# schematic.net
KiCad netlist of a schematic drawn in EAGLE
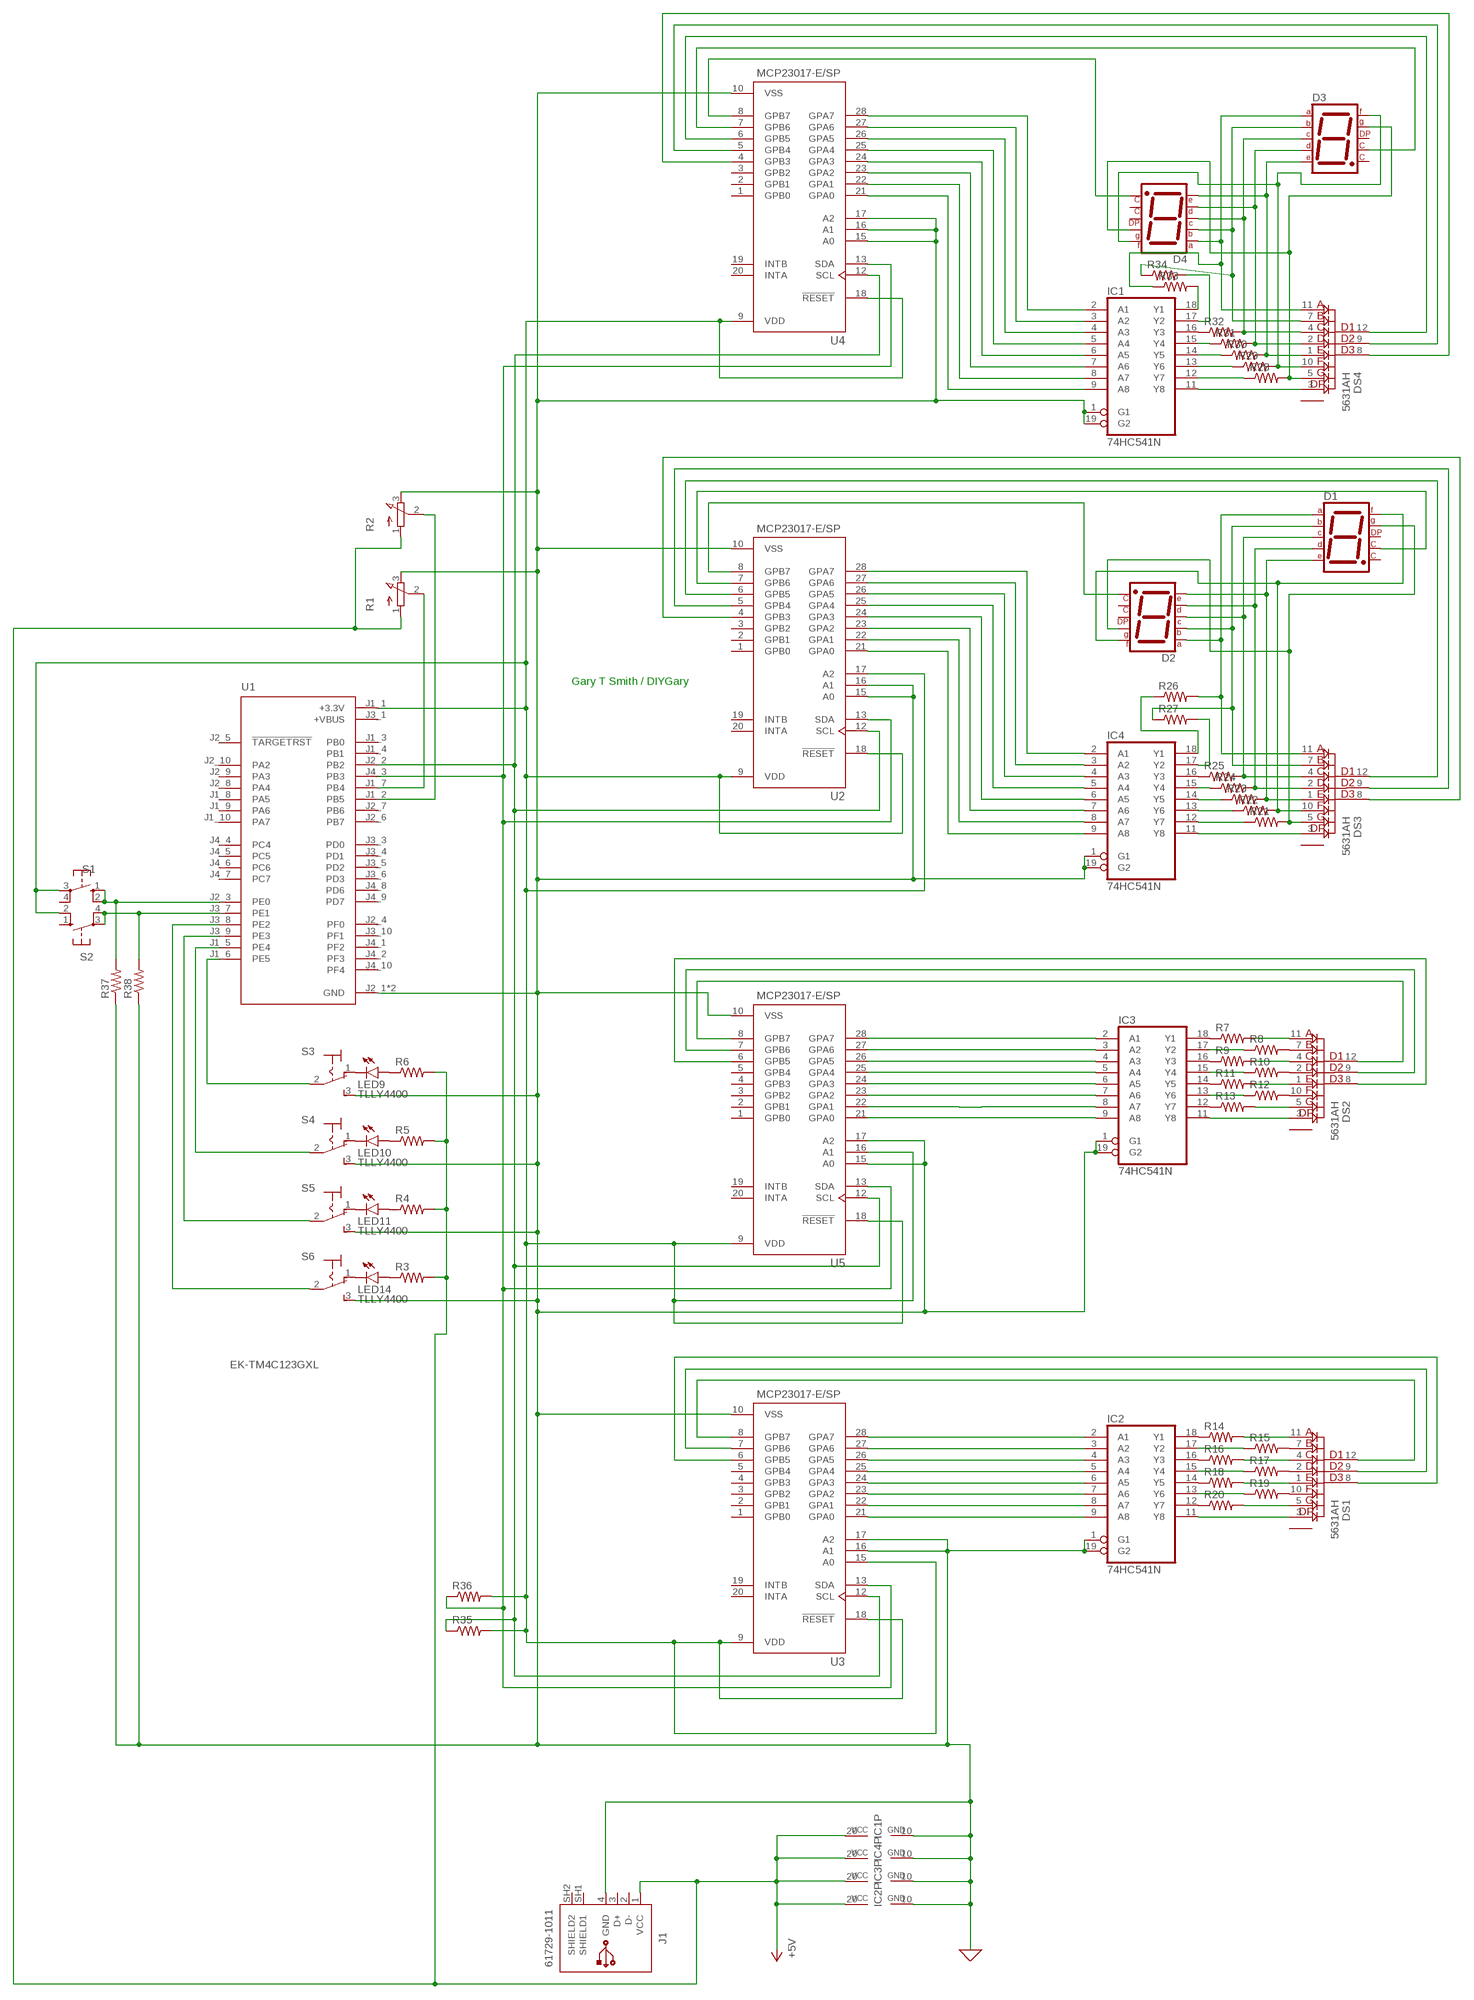
[diagram p0: schematic, sheet 1]

(export (version "E")
  (design (tool "Eeschema 10.0.6"))
  (components
    (comp (ref "D1")
      (value "5611AH")
      (footprint "eagle-import:5611AH")
      (libsource (lib "eagle-import") (part "5611AH"))
    )
    (comp (ref "D2")
      (value "5611AH")
      (footprint "eagle-import:5611AH")
      (libsource (lib "eagle-import") (part "5611AH"))
    )
    (comp (ref "D3")
      (value "5611AH")
      (footprint "eagle-import:5611AH")
      (libsource (lib "eagle-import") (part "5611AH"))
    )
    (comp (ref "D4")
      (value "5611AH")
      (footprint "eagle-import:5611AH")
      (libsource (lib "eagle-import") (part "5611AH"))
    )
    (comp (ref "DS1")
      (value "5631AH")
      (footprint "eagle-import:DIPS1524W50P254L3760H835Q12N")
      (fields
        (field (name "MANUFACTURER_PART_NUMBER") "BC56-12SRWA")
        (field (name "MOUSER_PART_NUMBER") "604-BC56-12SRWA")
      )
      (libsource (lib "eagle-import") (part "5631AH"))
    )
    (comp (ref "DS2")
      (value "5631AH")
      (footprint "eagle-import:DIPS1524W50P254L3760H835Q12N")
      (fields
        (field (name "MANUFACTURER_PART_NUMBER") "BC56-12SRWA")
        (field (name "MOUSER_PART_NUMBER") "604-BC56-12SRWA")
      )
      (libsource (lib "eagle-import") (part "5631AH"))
    )
    (comp (ref "DS3")
      (value "5631AH")
      (footprint "eagle-import:DIPS1524W50P254L3760H835Q12N")
      (fields
        (field (name "MANUFACTURER_PART_NUMBER") "BC56-12SRWA")
        (field (name "MOUSER_PART_NUMBER") "604-BC56-12SRWA")
      )
      (libsource (lib "eagle-import") (part "5631AH"))
    )
    (comp (ref "DS4")
      (value "5631AH")
      (footprint "eagle-import:DIPS1524W50P254L3760H835Q12N")
      (fields
        (field (name "MANUFACTURER_PART_NUMBER") "BC56-12SRWA")
        (field (name "MOUSER_PART_NUMBER") "604-BC56-12SRWA")
      )
      (libsource (lib "eagle-import") (part "5631AH"))
    )
    (comp (ref "IC1")
      (value "74HC541N")
      (footprint "eagle-import:DIL20")
      (libsource (lib "eagle-import") (part "74541NHC"))
    )
    (comp (ref "IC2")
      (value "74HC541N")
      (footprint "eagle-import:DIL20")
      (libsource (lib "eagle-import") (part "74541NHC"))
    )
    (comp (ref "IC3")
      (value "74HC541N")
      (footprint "eagle-import:DIL20")
      (libsource (lib "eagle-import") (part "74541NHC"))
    )
    (comp (ref "IC4")
      (value "74HC541N")
      (footprint "eagle-import:DIL20")
      (libsource (lib "eagle-import") (part "74541NHC"))
    )
    (comp (ref "J1")
      (value "61729-1011")
      (footprint "eagle-import:61729-1011BLF")
      (fields (field (name "MANUFACTURER") "Amphenol ICC (FCI)") (field (name "MPN") "61729-1011BLF"))
      (libsource (lib "eagle-import") (part "61729-1011"))
    )
    (comp (ref "LED9")
      (value "TLLY4400")
      (footprint "eagle-import:LED3MM")
      (fields (field (name "MF") "VISHAY SEMICONDUCTOR"))
      (libsource (lib "eagle-import") (part "TLLY4400"))
    )
    (comp (ref "LED10")
      (value "TLLY4400")
      (footprint "eagle-import:LED3MM")
      (fields (field (name "MF") "VISHAY SEMICONDUCTOR"))
      (libsource (lib "eagle-import") (part "TLLY4400"))
    )
    (comp (ref "LED11")
      (value "TLLY4400")
      (footprint "eagle-import:LED3MM")
      (fields (field (name "MF") "VISHAY SEMICONDUCTOR"))
      (libsource (lib "eagle-import") (part "TLLY4400"))
    )
    (comp (ref "LED14")
      (value "TLLY4400")
      (footprint "eagle-import:LED3MM")
      (fields (field (name "MF") "VISHAY SEMICONDUCTOR"))
      (libsource (lib "eagle-import") (part "TLLY4400"))
    )
    (comp (ref "R1")
      (value "3RP/1610N")
      (footprint "eagle-import:3RP_1610N")
      (libsource (lib "eagle-import") (part "3RP/1610N"))
    )
    (comp (ref "R2")
      (value "3RP/1610N")
      (footprint "eagle-import:3RP_1610N")
      (libsource (lib "eagle-import") (part "3RP/1610N"))
    )
    (comp (ref "R3")
      (value "R-US_0204/7")
      (footprint "eagle-import:0204_7")
      (libsource (lib "eagle-import") (part "R-US_0204/7"))
    )
    (comp (ref "R4")
      (value "R-US_0204/7")
      (footprint "eagle-import:0204_7")
      (libsource (lib "eagle-import") (part "R-US_0204/7"))
    )
    (comp (ref "R5")
      (value "R-US_0204/7")
      (footprint "eagle-import:0204_7")
      (libsource (lib "eagle-import") (part "R-US_0204/7"))
    )
    (comp (ref "R6")
      (value "R-US_0204/7")
      (footprint "eagle-import:0204_7")
      (libsource (lib "eagle-import") (part "R-US_0204/7"))
    )
    (comp (ref "R7")
      (value "R-US_0204/7")
      (footprint "eagle-import:0204_7")
      (libsource (lib "eagle-import") (part "R-US_0204/7"))
    )
    (comp (ref "R8")
      (value "R-US_0204/7")
      (footprint "eagle-import:0204_7")
      (libsource (lib "eagle-import") (part "R-US_0204/7"))
    )
    (comp (ref "R9")
      (value "R-US_0204/7")
      (footprint "eagle-import:0204_7")
      (libsource (lib "eagle-import") (part "R-US_0204/7"))
    )
    (comp (ref "R10")
      (value "R-US_0204/7")
      (footprint "eagle-import:0204_7")
      (libsource (lib "eagle-import") (part "R-US_0204/7"))
    )
    (comp (ref "R11")
      (value "R-US_0204/7")
      (footprint "eagle-import:0204_7")
      (libsource (lib "eagle-import") (part "R-US_0204/7"))
    )
    (comp (ref "R12")
      (value "R-US_0204/7")
      (footprint "eagle-import:0204_7")
      (libsource (lib "eagle-import") (part "R-US_0204/7"))
    )
    (comp (ref "R13")
      (value "R-US_0204/7")
      (footprint "eagle-import:0204_7")
      (libsource (lib "eagle-import") (part "R-US_0204/7"))
    )
    (comp (ref "R14")
      (value "R-US_0204/7")
      (footprint "eagle-import:0204_7")
      (libsource (lib "eagle-import") (part "R-US_0204/7"))
    )
    (comp (ref "R15")
      (value "R-US_0204/7")
      (footprint "eagle-import:0204_7")
      (libsource (lib "eagle-import") (part "R-US_0204/7"))
    )
    (comp (ref "R16")
      (value "R-US_0204/7")
      (footprint "eagle-import:0204_7")
      (libsource (lib "eagle-import") (part "R-US_0204/7"))
    )
    (comp (ref "R17")
      (value "R-US_0204/7")
      (footprint "eagle-import:0204_7")
      (libsource (lib "eagle-import") (part "R-US_0204/7"))
    )
    (comp (ref "R18")
      (value "R-US_0204/7")
      (footprint "eagle-import:0204_7")
      (libsource (lib "eagle-import") (part "R-US_0204/7"))
    )
    (comp (ref "R19")
      (value "R-US_0204/7")
      (footprint "eagle-import:0204_7")
      (libsource (lib "eagle-import") (part "R-US_0204/7"))
    )
    (comp (ref "R20")
      (value "R-US_0204/7")
      (footprint "eagle-import:0204_7")
      (libsource (lib "eagle-import") (part "R-US_0204/7"))
    )
    (comp (ref "R21")
      (value "R-US_0204/7")
      (footprint "eagle-import:0204_7")
      (libsource (lib "eagle-import") (part "R-US_0204/7"))
    )
    (comp (ref "R22")
      (value "R-US_0204/7")
      (footprint "eagle-import:0204_7")
      (libsource (lib "eagle-import") (part "R-US_0204/7"))
    )
    (comp (ref "R23")
      (value "R-US_0204/7")
      (footprint "eagle-import:0204_7")
      (libsource (lib "eagle-import") (part "R-US_0204/7"))
    )
    (comp (ref "R24")
      (value "R-US_0204/7")
      (footprint "eagle-import:0204_7")
      (libsource (lib "eagle-import") (part "R-US_0204/7"))
    )
    (comp (ref "R25")
      (value "R-US_0204/7")
      (footprint "eagle-import:0204_7")
      (libsource (lib "eagle-import") (part "R-US_0204/7"))
    )
    (comp (ref "R26")
      (value "R-US_0204/7")
      (footprint "eagle-import:0204_7")
      (libsource (lib "eagle-import") (part "R-US_0204/7"))
    )
    (comp (ref "R27")
      (value "R-US_0204/7")
      (footprint "eagle-import:0204_7")
      (libsource (lib "eagle-import") (part "R-US_0204/7"))
    )
    (comp (ref "R28")
      (value "R-US_0204/7")
      (footprint "eagle-import:0204_7")
      (libsource (lib "eagle-import") (part "R-US_0204/7"))
    )
    (comp (ref "R29")
      (value "R-US_0204/7")
      (footprint "eagle-import:0204_7")
      (libsource (lib "eagle-import") (part "R-US_0204/7"))
    )
    (comp (ref "R30")
      (value "R-US_0204/7")
      (footprint "eagle-import:0204_7")
      (libsource (lib "eagle-import") (part "R-US_0204/7"))
    )
    (comp (ref "R31")
      (value "R-US_0204/7")
      (footprint "eagle-import:0204_7")
      (libsource (lib "eagle-import") (part "R-US_0204/7"))
    )
    (comp (ref "R32")
      (value "R-US_0204/7")
      (footprint "eagle-import:0204_7")
      (libsource (lib "eagle-import") (part "R-US_0204/7"))
    )
    (comp (ref "R33")
      (value "R-US_0204/7")
      (footprint "eagle-import:0204_7")
      (libsource (lib "eagle-import") (part "R-US_0204/7"))
    )
    (comp (ref "R34")
      (value "R-US_0204/7")
      (footprint "eagle-import:0204_7")
      (libsource (lib "eagle-import") (part "R-US_0204/7"))
    )
    (comp (ref "R35")
      (value "R-US_0204/7")
      (footprint "eagle-import:0204_7")
      (libsource (lib "eagle-import") (part "R-US_0204/7"))
    )
    (comp (ref "R36")
      (value "R-US_0204/7")
      (footprint "eagle-import:0204_7")
      (libsource (lib "eagle-import") (part "R-US_0204/7"))
    )
    (comp (ref "R37")
      (value "R-US_0204/7")
      (footprint "eagle-import:0204_7")
      (libsource (lib "eagle-import") (part "R-US_0204/7"))
    )
    (comp (ref "R38")
      (value "R-US_0204/7")
      (footprint "eagle-import:0204_7")
      (libsource (lib "eagle-import") (part "R-US_0204/7"))
    )
    (comp (ref "S1")
      (value "10-XX")
      (footprint "eagle-import:B3F-10XX")
      (fields (field (name "MPN") "B3F-1000"))
      (libsource (lib "eagle-import") (part "10-XX"))
    )
    (comp (ref "S2")
      (value "10-XX")
      (footprint "eagle-import:B3F-10XX")
      (fields (field (name "MPN") "B3F-1000"))
      (libsource (lib "eagle-import") (part "10-XX"))
    )
    (comp (ref "S3")
      (value "320-916")
      (footprint "eagle-import:320-916")
      (libsource (lib "eagle-import") (part "320-916"))
    )
    (comp (ref "S4")
      (value "320-916")
      (footprint "eagle-import:320-916")
      (libsource (lib "eagle-import") (part "320-916"))
    )
    (comp (ref "S5")
      (value "320-916")
      (footprint "eagle-import:320-916")
      (libsource (lib "eagle-import") (part "320-916"))
    )
    (comp (ref "S6")
      (value "320-916")
      (footprint "eagle-import:320-916")
      (libsource (lib "eagle-import") (part "320-916"))
    )
    (comp (ref "U1")
      (value "EK-TM4C123GXL")
      (footprint "eagle-import:MODULE_EK-TM4C123GXL")
      (fields (field (name "MF") "Texas Instruments"))
      (libsource (lib "eagle-import") (part "EK-TM4C123GXL"))
    )
    (comp (ref "U2")
      (value "MCP23017-E/SP")
      (footprint "eagle-import:DIP787W45P254L3556H508Q28")
      (fields (field (name "MF") "Microchip Technology"))
      (libsource (lib "eagle-import") (part "MCP23017-E/SP"))
    )
    (comp (ref "U3")
      (value "MCP23017-E/SP")
      (footprint "eagle-import:DIP787W45P254L3556H508Q28")
      (fields (field (name "MF") "Microchip Technology"))
      (libsource (lib "eagle-import") (part "MCP23017-E/SP"))
    )
    (comp (ref "U4")
      (value "MCP23017-E/SP")
      (footprint "eagle-import:DIP787W45P254L3556H508Q28")
      (fields (field (name "MF") "Microchip Technology"))
      (libsource (lib "eagle-import") (part "MCP23017-E/SP"))
    )
    (comp (ref "U5")
      (value "MCP23017-E/SP")
      (footprint "eagle-import:DIP787W45P254L3556H508Q28")
      (fields (field (name "MF") "Microchip Technology"))
      (libsource (lib "eagle-import") (part "MCP23017-E/SP"))
    )
  )
  (nets
    (net (code "1") (name "+5V") (class "Default")
      (node (ref "IC1") (pin "20") (pinfunction "VCC_20") (pintype "power_in"))
      (node (ref "IC2") (pin "20") (pinfunction "VCC_20") (pintype "power_in"))
      (node (ref "IC3") (pin "20") (pinfunction "VCC_20") (pintype "power_in"))
      (node (ref "IC4") (pin "20") (pinfunction "VCC_20") (pintype "power_in"))
      (node (ref "J1") (pin "1") (pinfunction "VCC_1") (pintype "power_in"))
      (node (ref "R1") (pin "1") (pinfunction "A_1") (pintype "passive"))
      (node (ref "R2") (pin "1") (pinfunction "A_1") (pintype "passive"))
      (node (ref "R3") (pin "2") (pinfunction "2_2") (pintype "passive"))
      (node (ref "R4") (pin "2") (pinfunction "2_2") (pintype "passive"))
      (node (ref "R5") (pin "2") (pinfunction "2_2") (pintype "passive"))
      (node (ref "R6") (pin "2") (pinfunction "2_2") (pintype "passive"))
    )
    (net (code "2") (name "/+VBUS") (class "Default")
      (node (ref "U1") (pin "J3_1") (pinfunction "+VBUS_J3_1") (pintype "power_in"))
    )
    (net (code "3") (name "/SHIELD1") (class "Default")
      (node (ref "J1") (pin "SH1") (pinfunction "SHIELD1_SH1") (pintype "power_in"))
    )
    (net (code "4") (name "/SHIELD2") (class "Default")
      (node (ref "J1") (pin "SH2") (pinfunction "SHIELD2_SH2") (pintype "power_in"))
    )
    (net (code "5") (name "GND") (class "Default")
      (node (ref "IC1") (pin "1") (pinfunction "G1_1") (pintype "input"))
      (node (ref "IC1") (pin "10") (pinfunction "GND_10") (pintype "power_in"))
      (node (ref "IC1") (pin "19") (pinfunction "G2_19") (pintype "input"))
      (node (ref "IC2") (pin "1") (pinfunction "G1_1") (pintype "input"))
      (node (ref "IC2") (pin "10") (pinfunction "GND_10") (pintype "power_in"))
      (node (ref "IC2") (pin "19") (pinfunction "G2_19") (pintype "input"))
      (node (ref "IC3") (pin "1") (pinfunction "G1_1") (pintype "input"))
      (node (ref "IC3") (pin "10") (pinfunction "GND_10") (pintype "power_in"))
      (node (ref "IC3") (pin "19") (pinfunction "G2_19") (pintype "input"))
      (node (ref "IC4") (pin "1") (pinfunction "G1_1") (pintype "input"))
      (node (ref "IC4") (pin "10") (pinfunction "GND_10") (pintype "power_in"))
      (node (ref "IC4") (pin "19") (pinfunction "G2_19") (pintype "input"))
      (node (ref "J1") (pin "4") (pinfunction "GND_4") (pintype "power_in"))
      (node (ref "R1") (pin "3") (pinfunction "E_3") (pintype "passive"))
      (node (ref "R2") (pin "3") (pinfunction "E_3") (pintype "passive"))
      (node (ref "R37") (pin "1") (pinfunction "1_1") (pintype "passive"))
      (node (ref "R38") (pin "1") (pinfunction "1_1") (pintype "passive"))
      (node (ref "S3") (pin "3") (pinfunction "S_3") (pintype "passive"))
      (node (ref "S4") (pin "3") (pinfunction "S_3") (pintype "passive"))
      (node (ref "S5") (pin "3") (pinfunction "S_3") (pintype "passive"))
      (node (ref "S6") (pin "3") (pinfunction "S_3") (pintype "passive"))
      (node (ref "U1") (pin "J2_1") (pinfunction "GND_J2_1") (pintype "power_in"))
      (node (ref "U1") (pin "J3_2") (pinfunction "GND_J3_2") (pintype "power_in"))
      (node (ref "U2") (pin "10") (pinfunction "VSS_10") (pintype "power_in"))
      (node (ref "U2") (pin "15") (pinfunction "A0_15") (pintype "input"))
      (node (ref "U2") (pin "16") (pinfunction "A1_16") (pintype "input"))
      (node (ref "U3") (pin "10") (pinfunction "VSS_10") (pintype "power_in"))
      (node (ref "U3") (pin "16") (pinfunction "A1_16") (pintype "input"))
      (node (ref "U3") (pin "17") (pinfunction "A2_17") (pintype "input"))
      (node (ref "U4") (pin "10") (pinfunction "VSS_10") (pintype "power_in"))
      (node (ref "U4") (pin "15") (pinfunction "A0_15") (pintype "input"))
      (node (ref "U4") (pin "16") (pinfunction "A1_16") (pintype "input"))
      (node (ref "U4") (pin "17") (pinfunction "A2_17") (pintype "input"))
      (node (ref "U5") (pin "10") (pinfunction "VSS_10") (pintype "power_in"))
      (node (ref "U5") (pin "15") (pinfunction "A0_15") (pintype "input"))
      (node (ref "U5") (pin "17") (pinfunction "A2_17") (pintype "input"))
    )
    (net (code "6") (name "Net-(D1-A)") (class "Default")
      (node (ref "D1") (pin "7") (pinfunction "A_7") (pintype "passive"))
      (node (ref "D2") (pin "7") (pinfunction "A_7") (pintype "passive"))
      (node (ref "DS3") (pin "11") (pinfunction "A_A_11") (pintype "bidirectional"))
      (node (ref "R26") (pin "2") (pinfunction "2_2") (pintype "passive"))
    )
    (net (code "7") (name "Net-(D1-B)") (class "Default")
      (node (ref "D1") (pin "6") (pinfunction "B_6") (pintype "passive"))
      (node (ref "D2") (pin "6") (pinfunction "B_6") (pintype "passive"))
      (node (ref "DS3") (pin "7") (pinfunction "A_B_7") (pintype "bidirectional"))
      (node (ref "R27") (pin "1") (pinfunction "1_1") (pintype "passive"))
    )
    (net (code "8") (name "Net-(D1-C)") (class "Default")
      (node (ref "D1") (pin "4") (pinfunction "C_4") (pintype "passive"))
      (node (ref "D2") (pin "4") (pinfunction "C_4") (pintype "passive"))
      (node (ref "DS3") (pin "4") (pinfunction "A_C_4") (pintype "bidirectional"))
      (node (ref "R25") (pin "2") (pinfunction "2_2") (pintype "passive"))
    )
    (net (code "9") (name "Net-(D1-CK1)") (class "Default")
      (node (ref "D1") (pin "3") (pinfunction "CK1_3") (pintype "passive"))
      (node (ref "U2") (pin "7") (pinfunction "GPB6_7") (pintype "bidirectional"))
    )
    (net (code "10") (name "Net-(D1-D)") (class "Default")
      (node (ref "D1") (pin "2") (pinfunction "D_2") (pintype "passive"))
      (node (ref "D2") (pin "2") (pinfunction "D_2") (pintype "passive"))
      (node (ref "DS3") (pin "2") (pinfunction "A_D_2") (pintype "bidirectional"))
      (node (ref "R24") (pin "2") (pinfunction "2_2") (pintype "passive"))
    )
    (net (code "11") (name "Net-(D1-E)") (class "Default")
      (node (ref "D1") (pin "1") (pinfunction "E_1") (pintype "passive"))
      (node (ref "D2") (pin "1") (pinfunction "E_1") (pintype "passive"))
      (node (ref "DS3") (pin "1") (pinfunction "A_E_1") (pintype "bidirectional"))
      (node (ref "R23") (pin "2") (pinfunction "2_2") (pintype "passive"))
    )
    (net (code "12") (name "Net-(D1-F)") (class "Default")
      (node (ref "D1") (pin "9") (pinfunction "F_9") (pintype "passive"))
      (node (ref "D2") (pin "9") (pinfunction "F_9") (pintype "passive"))
      (node (ref "DS3") (pin "10") (pinfunction "A_F_10") (pintype "bidirectional"))
      (node (ref "R22") (pin "2") (pinfunction "2_2") (pintype "passive"))
    )
    (net (code "13") (name "Net-(D1-G)") (class "Default")
      (node (ref "D1") (pin "10") (pinfunction "G_10") (pintype "passive"))
      (node (ref "D2") (pin "10") (pinfunction "G_10") (pintype "passive"))
      (node (ref "DS3") (pin "5") (pinfunction "A_G_5") (pintype "bidirectional"))
      (node (ref "R21") (pin "2") (pinfunction "2_2") (pintype "passive"))
    )
    (net (code "14") (name "Net-(D2-CK2)") (class "Default")
      (node (ref "D2") (pin "8") (pinfunction "CK2_8") (pintype "passive"))
      (node (ref "U2") (pin "8") (pinfunction "GPB7_8") (pintype "bidirectional"))
    )
    (net (code "15") (name "Net-(D3-A)") (class "Default")
      (node (ref "D3") (pin "7") (pinfunction "A_7") (pintype "passive"))
      (node (ref "D4") (pin "7") (pinfunction "A_7") (pintype "passive"))
      (node (ref "DS4") (pin "11") (pinfunction "A_A_11") (pintype "bidirectional"))
      (node (ref "R33") (pin "1") (pinfunction "1_1") (pintype "passive"))
    )
    (net (code "16") (name "Net-(D3-B)") (class "Default")
      (node (ref "D3") (pin "6") (pinfunction "B_6") (pintype "passive"))
      (node (ref "D4") (pin "6") (pinfunction "B_6") (pintype "passive"))
      (node (ref "DS4") (pin "7") (pinfunction "A_B_7") (pintype "bidirectional"))
      (node (ref "R34") (pin "1") (pinfunction "1_1") (pintype "passive"))
    )
    (net (code "17") (name "Net-(D3-C)") (class "Default")
      (node (ref "D3") (pin "4") (pinfunction "C_4") (pintype "passive"))
      (node (ref "D4") (pin "4") (pinfunction "C_4") (pintype "passive"))
      (node (ref "DS4") (pin "4") (pinfunction "A_C_4") (pintype "bidirectional"))
      (node (ref "R32") (pin "2") (pinfunction "2_2") (pintype "passive"))
    )
    (net (code "18") (name "Net-(D3-CK1)") (class "Default")
      (node (ref "D3") (pin "3") (pinfunction "CK1_3") (pintype "passive"))
      (node (ref "U4") (pin "7") (pinfunction "GPB6_7") (pintype "bidirectional"))
    )
    (net (code "19") (name "Net-(D3-D)") (class "Default")
      (node (ref "D3") (pin "2") (pinfunction "D_2") (pintype "passive"))
      (node (ref "D4") (pin "2") (pinfunction "D_2") (pintype "passive"))
      (node (ref "DS4") (pin "2") (pinfunction "A_D_2") (pintype "bidirectional"))
      (node (ref "R31") (pin "2") (pinfunction "2_2") (pintype "passive"))
    )
    (net (code "20") (name "Net-(D3-E)") (class "Default")
      (node (ref "D3") (pin "1") (pinfunction "E_1") (pintype "passive"))
      (node (ref "D4") (pin "1") (pinfunction "E_1") (pintype "passive"))
      (node (ref "DS4") (pin "1") (pinfunction "A_E_1") (pintype "bidirectional"))
      (node (ref "R30") (pin "2") (pinfunction "2_2") (pintype "passive"))
    )
    (net (code "21") (name "Net-(D3-F)") (class "Default")
      (node (ref "D3") (pin "9") (pinfunction "F_9") (pintype "passive"))
      (node (ref "D4") (pin "9") (pinfunction "F_9") (pintype "passive"))
      (node (ref "DS4") (pin "10") (pinfunction "A_F_10") (pintype "bidirectional"))
      (node (ref "R29") (pin "2") (pinfunction "2_2") (pintype "passive"))
    )
    (net (code "22") (name "Net-(D3-G)") (class "Default")
      (node (ref "D3") (pin "10") (pinfunction "G_10") (pintype "passive"))
      (node (ref "D4") (pin "10") (pinfunction "G_10") (pintype "passive"))
      (node (ref "DS4") (pin "5") (pinfunction "A_G_5") (pintype "bidirectional"))
      (node (ref "R28") (pin "2") (pinfunction "2_2") (pintype "passive"))
    )
    (net (code "23") (name "Net-(D4-CK2)") (class "Default")
      (node (ref "D4") (pin "8") (pinfunction "CK2_8") (pintype "passive"))
      (node (ref "U4") (pin "8") (pinfunction "GPB7_8") (pintype "bidirectional"))
    )
    (net (code "24") (name "Net-(DS1-A_A)") (class "Default")
      (node (ref "DS1") (pin "11") (pinfunction "A_A_11") (pintype "bidirectional"))
      (node (ref "R14") (pin "2") (pinfunction "2_2") (pintype "passive"))
    )
    (net (code "25") (name "Net-(DS1-A_B)") (class "Default")
      (node (ref "DS1") (pin "7") (pinfunction "A_B_7") (pintype "bidirectional"))
      (node (ref "R15") (pin "2") (pinfunction "2_2") (pintype "passive"))
    )
    (net (code "26") (name "Net-(DS1-A_C)") (class "Default")
      (node (ref "DS1") (pin "4") (pinfunction "A_C_4") (pintype "bidirectional"))
      (node (ref "R16") (pin "2") (pinfunction "2_2") (pintype "passive"))
    )
    (net (code "27") (name "Net-(DS1-A_D)") (class "Default")
      (node (ref "DS1") (pin "2") (pinfunction "A_D_2") (pintype "bidirectional"))
      (node (ref "R17") (pin "2") (pinfunction "2_2") (pintype "passive"))
    )
    (net (code "28") (name "Net-(DS1-A_DP)") (class "Default")
      (node (ref "DS1") (pin "3") (pinfunction "A_DP_3") (pintype "bidirectional"))
      (node (ref "IC2") (pin "11") (pinfunction "Y8_11") (pintype "tri_state"))
    )
    (net (code "29") (name "Net-(DS1-A_E)") (class "Default")
      (node (ref "DS1") (pin "1") (pinfunction "A_E_1") (pintype "bidirectional"))
      (node (ref "R18") (pin "2") (pinfunction "2_2") (pintype "passive"))
    )
    (net (code "30") (name "Net-(DS1-A_F)") (class "Default")
      (node (ref "DS1") (pin "10") (pinfunction "A_F_10") (pintype "bidirectional"))
      (node (ref "R19") (pin "2") (pinfunction "2_2") (pintype "passive"))
    )
    (net (code "31") (name "Net-(DS1-A_G)") (class "Default")
      (node (ref "DS1") (pin "5") (pinfunction "A_G_5") (pintype "bidirectional"))
      (node (ref "R20") (pin "2") (pinfunction "2_2") (pintype "passive"))
    )
    (net (code "32") (name "Net-(DS1-CC_D1)") (class "Default")
      (node (ref "DS1") (pin "12") (pinfunction "CC_D1_12") (pintype "bidirectional"))
      (node (ref "U3") (pin "8") (pinfunction "GPB7_8") (pintype "bidirectional"))
    )
    (net (code "33") (name "Net-(DS1-CC_D2)") (class "Default")
      (node (ref "DS1") (pin "9") (pinfunction "CC_D2_9") (pintype "bidirectional"))
      (node (ref "U3") (pin "7") (pinfunction "GPB6_7") (pintype "bidirectional"))
    )
    (net (code "34") (name "Net-(DS1-CC_D3)") (class "Default")
      (node (ref "DS1") (pin "8") (pinfunction "CC_D3_8") (pintype "bidirectional"))
      (node (ref "U3") (pin "6") (pinfunction "GPB5_6") (pintype "bidirectional"))
    )
    (net (code "35") (name "Net-(DS2-A_A)") (class "Default")
      (node (ref "DS2") (pin "11") (pinfunction "A_A_11") (pintype "bidirectional"))
      (node (ref "R7") (pin "2") (pinfunction "2_2") (pintype "passive"))
    )
    (net (code "36") (name "Net-(DS2-A_B)") (class "Default")
      (node (ref "DS2") (pin "7") (pinfunction "A_B_7") (pintype "bidirectional"))
      (node (ref "R8") (pin "2") (pinfunction "2_2") (pintype "passive"))
    )
    (net (code "37") (name "Net-(DS2-A_C)") (class "Default")
      (node (ref "DS2") (pin "4") (pinfunction "A_C_4") (pintype "bidirectional"))
      (node (ref "R9") (pin "2") (pinfunction "2_2") (pintype "passive"))
    )
    (net (code "38") (name "Net-(DS2-A_D)") (class "Default")
      (node (ref "DS2") (pin "2") (pinfunction "A_D_2") (pintype "bidirectional"))
      (node (ref "R10") (pin "2") (pinfunction "2_2") (pintype "passive"))
    )
    (net (code "39") (name "Net-(DS2-A_DP)") (class "Default")
      (node (ref "DS2") (pin "3") (pinfunction "A_DP_3") (pintype "bidirectional"))
      (node (ref "IC3") (pin "11") (pinfunction "Y8_11") (pintype "tri_state"))
    )
    (net (code "40") (name "Net-(DS2-A_E)") (class "Default")
      (node (ref "DS2") (pin "1") (pinfunction "A_E_1") (pintype "bidirectional"))
      (node (ref "R11") (pin "2") (pinfunction "2_2") (pintype "passive"))
    )
    (net (code "41") (name "Net-(DS2-A_F)") (class "Default")
      (node (ref "DS2") (pin "10") (pinfunction "A_F_10") (pintype "bidirectional"))
      (node (ref "R12") (pin "2") (pinfunction "2_2") (pintype "passive"))
    )
    (net (code "42") (name "Net-(DS2-A_G)") (class "Default")
      (node (ref "DS2") (pin "5") (pinfunction "A_G_5") (pintype "bidirectional"))
      (node (ref "R13") (pin "2") (pinfunction "2_2") (pintype "passive"))
    )
    (net (code "43") (name "Net-(DS2-CC_D1)") (class "Default")
      (node (ref "DS2") (pin "12") (pinfunction "CC_D1_12") (pintype "bidirectional"))
      (node (ref "U5") (pin "8") (pinfunction "GPB7_8") (pintype "bidirectional"))
    )
    (net (code "44") (name "Net-(DS2-CC_D2)") (class "Default")
      (node (ref "DS2") (pin "9") (pinfunction "CC_D2_9") (pintype "bidirectional"))
      (node (ref "U5") (pin "7") (pinfunction "GPB6_7") (pintype "bidirectional"))
    )
    (net (code "45") (name "Net-(DS2-CC_D3)") (class "Default")
      (node (ref "DS2") (pin "8") (pinfunction "CC_D3_8") (pintype "bidirectional"))
      (node (ref "U5") (pin "6") (pinfunction "GPB5_6") (pintype "bidirectional"))
    )
    (net (code "46") (name "Net-(DS3-A_DP)") (class "Default")
      (node (ref "DS3") (pin "3") (pinfunction "A_DP_3") (pintype "bidirectional"))
      (node (ref "IC4") (pin "11") (pinfunction "Y8_11") (pintype "tri_state"))
    )
    (net (code "47") (name "Net-(DS3-CC_D1)") (class "Default")
      (node (ref "DS3") (pin "12") (pinfunction "CC_D1_12") (pintype "bidirectional"))
      (node (ref "U2") (pin "6") (pinfunction "GPB5_6") (pintype "bidirectional"))
    )
    (net (code "48") (name "Net-(DS3-CC_D2)") (class "Default")
      (node (ref "DS3") (pin "9") (pinfunction "CC_D2_9") (pintype "bidirectional"))
      (node (ref "U2") (pin "5") (pinfunction "GPB4_5") (pintype "bidirectional"))
    )
    (net (code "49") (name "Net-(DS3-CC_D3)") (class "Default")
      (node (ref "DS3") (pin "8") (pinfunction "CC_D3_8") (pintype "bidirectional"))
      (node (ref "U2") (pin "4") (pinfunction "GPB3_4") (pintype "bidirectional"))
    )
    (net (code "50") (name "Net-(DS4-A_DP)") (class "Default")
      (node (ref "DS4") (pin "3") (pinfunction "A_DP_3") (pintype "bidirectional"))
      (node (ref "IC1") (pin "11") (pinfunction "Y8_11") (pintype "tri_state"))
    )
    (net (code "51") (name "Net-(DS4-CC_D1)") (class "Default")
      (node (ref "DS4") (pin "12") (pinfunction "CC_D1_12") (pintype "bidirectional"))
      (node (ref "U4") (pin "6") (pinfunction "GPB5_6") (pintype "bidirectional"))
    )
    (net (code "52") (name "Net-(DS4-CC_D2)") (class "Default")
      (node (ref "DS4") (pin "9") (pinfunction "CC_D2_9") (pintype "bidirectional"))
      (node (ref "U4") (pin "5") (pinfunction "GPB4_5") (pintype "bidirectional"))
    )
    (net (code "53") (name "Net-(DS4-CC_D3)") (class "Default")
      (node (ref "DS4") (pin "8") (pinfunction "CC_D3_8") (pintype "bidirectional"))
      (node (ref "U4") (pin "4") (pinfunction "GPB3_4") (pintype "bidirectional"))
    )
    (net (code "54") (name "Net-(IC1A-A1)") (class "Default")
      (node (ref "IC1") (pin "2") (pinfunction "A1_2") (pintype "input"))
      (node (ref "U4") (pin "28") (pinfunction "GPA7_28") (pintype "bidirectional"))
    )
    (net (code "55") (name "Net-(IC1A-A2)") (class "Default")
      (node (ref "IC1") (pin "3") (pinfunction "A2_3") (pintype "input"))
      (node (ref "U4") (pin "27") (pinfunction "GPA6_27") (pintype "bidirectional"))
    )
    (net (code "56") (name "Net-(IC1A-A3)") (class "Default")
      (node (ref "IC1") (pin "4") (pinfunction "A3_4") (pintype "input"))
      (node (ref "U4") (pin "26") (pinfunction "GPA5_26") (pintype "bidirectional"))
    )
    (net (code "57") (name "Net-(IC1A-A4)") (class "Default")
      (node (ref "IC1") (pin "5") (pinfunction "A4_5") (pintype "input"))
      (node (ref "U4") (pin "25") (pinfunction "GPA4_25") (pintype "bidirectional"))
    )
    (net (code "58") (name "Net-(IC1A-A5)") (class "Default")
      (node (ref "IC1") (pin "6") (pinfunction "A5_6") (pintype "input"))
      (node (ref "U4") (pin "24") (pinfunction "GPA3_24") (pintype "bidirectional"))
    )
    (net (code "59") (name "Net-(IC1A-A6)") (class "Default")
      (node (ref "IC1") (pin "7") (pinfunction "A6_7") (pintype "input"))
      (node (ref "U4") (pin "23") (pinfunction "GPA2_23") (pintype "bidirectional"))
    )
    (net (code "60") (name "Net-(IC1A-A7)") (class "Default")
      (node (ref "IC1") (pin "8") (pinfunction "A7_8") (pintype "input"))
      (node (ref "U4") (pin "22") (pinfunction "GPA1_22") (pintype "bidirectional"))
    )
    (net (code "61") (name "Net-(IC1A-A8)") (class "Default")
      (node (ref "IC1") (pin "9") (pinfunction "A8_9") (pintype "input"))
      (node (ref "U4") (pin "21") (pinfunction "GPA0_21") (pintype "bidirectional"))
    )
    (net (code "62") (name "Net-(IC1A-Y1)") (class "Default")
      (node (ref "IC1") (pin "18") (pinfunction "Y1_18") (pintype "tri_state"))
      (node (ref "R33") (pin "2") (pinfunction "2_2") (pintype "passive"))
    )
    (net (code "63") (name "Net-(IC1A-Y2)") (class "Default")
      (node (ref "IC1") (pin "17") (pinfunction "Y2_17") (pintype "tri_state"))
      (node (ref "R34") (pin "2") (pinfunction "2_2") (pintype "passive"))
    )
    (net (code "64") (name "Net-(IC1A-Y3)") (class "Default")
      (node (ref "IC1") (pin "16") (pinfunction "Y3_16") (pintype "tri_state"))
      (node (ref "R32") (pin "1") (pinfunction "1_1") (pintype "passive"))
    )
    (net (code "65") (name "Net-(IC1A-Y4)") (class "Default")
      (node (ref "IC1") (pin "15") (pinfunction "Y4_15") (pintype "tri_state"))
      (node (ref "R31") (pin "1") (pinfunction "1_1") (pintype "passive"))
    )
    (net (code "66") (name "Net-(IC1A-Y5)") (class "Default")
      (node (ref "IC1") (pin "14") (pinfunction "Y5_14") (pintype "tri_state"))
      (node (ref "R30") (pin "1") (pinfunction "1_1") (pintype "passive"))
    )
    (net (code "67") (name "Net-(IC1A-Y6)") (class "Default")
      (node (ref "IC1") (pin "13") (pinfunction "Y6_13") (pintype "tri_state"))
      (node (ref "R29") (pin "1") (pinfunction "1_1") (pintype "passive"))
    )
    (net (code "68") (name "Net-(IC1A-Y7)") (class "Default")
      (node (ref "IC1") (pin "12") (pinfunction "Y7_12") (pintype "tri_state"))
      (node (ref "R28") (pin "1") (pinfunction "1_1") (pintype "passive"))
    )
    (net (code "69") (name "Net-(IC2A-A1)") (class "Default")
      (node (ref "IC2") (pin "2") (pinfunction "A1_2") (pintype "input"))
      (node (ref "U3") (pin "28") (pinfunction "GPA7_28") (pintype "bidirectional"))
    )
    (net (code "70") (name "Net-(IC2A-A2)") (class "Default")
      (node (ref "IC2") (pin "3") (pinfunction "A2_3") (pintype "input"))
      (node (ref "U3") (pin "27") (pinfunction "GPA6_27") (pintype "bidirectional"))
    )
    (net (code "71") (name "Net-(IC2A-A3)") (class "Default")
      (node (ref "IC2") (pin "4") (pinfunction "A3_4") (pintype "input"))
      (node (ref "U3") (pin "26") (pinfunction "GPA5_26") (pintype "bidirectional"))
    )
    (net (code "72") (name "Net-(IC2A-A4)") (class "Default")
      (node (ref "IC2") (pin "5") (pinfunction "A4_5") (pintype "input"))
      (node (ref "U3") (pin "25") (pinfunction "GPA4_25") (pintype "bidirectional"))
    )
    (net (code "73") (name "Net-(IC2A-A5)") (class "Default")
      (node (ref "IC2") (pin "6") (pinfunction "A5_6") (pintype "input"))
      (node (ref "U3") (pin "24") (pinfunction "GPA3_24") (pintype "bidirectional"))
    )
    (net (code "74") (name "Net-(IC2A-A6)") (class "Default")
      (node (ref "IC2") (pin "7") (pinfunction "A6_7") (pintype "input"))
      (node (ref "U3") (pin "23") (pinfunction "GPA2_23") (pintype "bidirectional"))
    )
    (net (code "75") (name "Net-(IC2A-A7)") (class "Default")
      (node (ref "IC2") (pin "8") (pinfunction "A7_8") (pintype "input"))
      (node (ref "U3") (pin "22") (pinfunction "GPA1_22") (pintype "bidirectional"))
    )
    (net (code "76") (name "Net-(IC2A-A8)") (class "Default")
      (node (ref "IC2") (pin "9") (pinfunction "A8_9") (pintype "input"))
      (node (ref "U3") (pin "21") (pinfunction "GPA0_21") (pintype "bidirectional"))
    )
    (net (code "77") (name "Net-(IC2A-Y1)") (class "Default")
      (node (ref "IC2") (pin "18") (pinfunction "Y1_18") (pintype "tri_state"))
      (node (ref "R14") (pin "1") (pinfunction "1_1") (pintype "passive"))
    )
    (net (code "78") (name "Net-(IC2A-Y2)") (class "Default")
      (node (ref "IC2") (pin "17") (pinfunction "Y2_17") (pintype "tri_state"))
      (node (ref "R15") (pin "1") (pinfunction "1_1") (pintype "passive"))
    )
    (net (code "79") (name "Net-(IC2A-Y3)") (class "Default")
      (node (ref "IC2") (pin "16") (pinfunction "Y3_16") (pintype "tri_state"))
      (node (ref "R16") (pin "1") (pinfunction "1_1") (pintype "passive"))
    )
    (net (code "80") (name "Net-(IC2A-Y4)") (class "Default")
      (node (ref "IC2") (pin "15") (pinfunction "Y4_15") (pintype "tri_state"))
      (node (ref "R17") (pin "1") (pinfunction "1_1") (pintype "passive"))
    )
    (net (code "81") (name "Net-(IC2A-Y5)") (class "Default")
      (node (ref "IC2") (pin "14") (pinfunction "Y5_14") (pintype "tri_state"))
      (node (ref "R18") (pin "1") (pinfunction "1_1") (pintype "passive"))
    )
    (net (code "82") (name "Net-(IC2A-Y6)") (class "Default")
      (node (ref "IC2") (pin "13") (pinfunction "Y6_13") (pintype "tri_state"))
      (node (ref "R19") (pin "1") (pinfunction "1_1") (pintype "passive"))
    )
    (net (code "83") (name "Net-(IC2A-Y7)") (class "Default")
      (node (ref "IC2") (pin "12") (pinfunction "Y7_12") (pintype "tri_state"))
      (node (ref "R20") (pin "1") (pinfunction "1_1") (pintype "passive"))
    )
    (net (code "84") (name "Net-(IC3A-A1)") (class "Default")
      (node (ref "IC3") (pin "2") (pinfunction "A1_2") (pintype "input"))
      (node (ref "U5") (pin "28") (pinfunction "GPA7_28") (pintype "bidirectional"))
    )
    (net (code "85") (name "Net-(IC3A-A2)") (class "Default")
      (node (ref "IC3") (pin "3") (pinfunction "A2_3") (pintype "input"))
      (node (ref "U5") (pin "27") (pinfunction "GPA6_27") (pintype "bidirectional"))
    )
    (net (code "86") (name "Net-(IC3A-A3)") (class "Default")
      (node (ref "IC3") (pin "4") (pinfunction "A3_4") (pintype "input"))
      (node (ref "U5") (pin "26") (pinfunction "GPA5_26") (pintype "bidirectional"))
    )
    (net (code "87") (name "Net-(IC3A-A4)") (class "Default")
      (node (ref "IC3") (pin "5") (pinfunction "A4_5") (pintype "input"))
      (node (ref "U5") (pin "25") (pinfunction "GPA4_25") (pintype "bidirectional"))
    )
    (net (code "88") (name "Net-(IC3A-A5)") (class "Default")
      (node (ref "IC3") (pin "6") (pinfunction "A5_6") (pintype "input"))
      (node (ref "U5") (pin "24") (pinfunction "GPA3_24") (pintype "bidirectional"))
    )
    (net (code "89") (name "Net-(IC3A-A6)") (class "Default")
      (node (ref "IC3") (pin "7") (pinfunction "A6_7") (pintype "input"))
      (node (ref "U5") (pin "23") (pinfunction "GPA2_23") (pintype "bidirectional"))
    )
    (net (code "90") (name "Net-(IC3A-A7)") (class "Default")
      (node (ref "IC3") (pin "8") (pinfunction "A7_8") (pintype "input"))
      (node (ref "U5") (pin "22") (pinfunction "GPA1_22") (pintype "bidirectional"))
    )
    (net (code "91") (name "Net-(IC3A-A8)") (class "Default")
      (node (ref "IC3") (pin "9") (pinfunction "A8_9") (pintype "input"))
      (node (ref "U5") (pin "21") (pinfunction "GPA0_21") (pintype "bidirectional"))
    )
    (net (code "92") (name "Net-(IC3A-Y1)") (class "Default")
      (node (ref "IC3") (pin "18") (pinfunction "Y1_18") (pintype "tri_state"))
      (node (ref "R7") (pin "1") (pinfunction "1_1") (pintype "passive"))
    )
    (net (code "93") (name "Net-(IC3A-Y2)") (class "Default")
      (node (ref "IC3") (pin "17") (pinfunction "Y2_17") (pintype "tri_state"))
      (node (ref "R8") (pin "1") (pinfunction "1_1") (pintype "passive"))
    )
    (net (code "94") (name "Net-(IC3A-Y3)") (class "Default")
      (node (ref "IC3") (pin "16") (pinfunction "Y3_16") (pintype "tri_state"))
      (node (ref "R9") (pin "1") (pinfunction "1_1") (pintype "passive"))
    )
    (net (code "95") (name "Net-(IC3A-Y4)") (class "Default")
      (node (ref "IC3") (pin "15") (pinfunction "Y4_15") (pintype "tri_state"))
      (node (ref "R10") (pin "1") (pinfunction "1_1") (pintype "passive"))
    )
    (net (code "96") (name "Net-(IC3A-Y5)") (class "Default")
      (node (ref "IC3") (pin "14") (pinfunction "Y5_14") (pintype "tri_state"))
      (node (ref "R11") (pin "1") (pinfunction "1_1") (pintype "passive"))
    )
    (net (code "97") (name "Net-(IC3A-Y6)") (class "Default")
      (node (ref "IC3") (pin "13") (pinfunction "Y6_13") (pintype "tri_state"))
      (node (ref "R12") (pin "1") (pinfunction "1_1") (pintype "passive"))
    )
    (net (code "98") (name "Net-(IC3A-Y7)") (class "Default")
      (node (ref "IC3") (pin "12") (pinfunction "Y7_12") (pintype "tri_state"))
      (node (ref "R13") (pin "1") (pinfunction "1_1") (pintype "passive"))
    )
    (net (code "99") (name "Net-(IC4A-A1)") (class "Default")
      (node (ref "IC4") (pin "2") (pinfunction "A1_2") (pintype "input"))
      (node (ref "U2") (pin "28") (pinfunction "GPA7_28") (pintype "bidirectional"))
    )
    (net (code "100") (name "Net-(IC4A-A2)") (class "Default")
      (node (ref "IC4") (pin "3") (pinfunction "A2_3") (pintype "input"))
      (node (ref "U2") (pin "27") (pinfunction "GPA6_27") (pintype "bidirectional"))
    )
    (net (code "101") (name "Net-(IC4A-A3)") (class "Default")
      (node (ref "IC4") (pin "4") (pinfunction "A3_4") (pintype "input"))
      (node (ref "U2") (pin "26") (pinfunction "GPA5_26") (pintype "bidirectional"))
    )
    (net (code "102") (name "Net-(IC4A-A4)") (class "Default")
      (node (ref "IC4") (pin "5") (pinfunction "A4_5") (pintype "input"))
      (node (ref "U2") (pin "25") (pinfunction "GPA4_25") (pintype "bidirectional"))
    )
    (net (code "103") (name "Net-(IC4A-A5)") (class "Default")
      (node (ref "IC4") (pin "6") (pinfunction "A5_6") (pintype "input"))
      (node (ref "U2") (pin "24") (pinfunction "GPA3_24") (pintype "bidirectional"))
    )
    (net (code "104") (name "Net-(IC4A-A6)") (class "Default")
      (node (ref "IC4") (pin "7") (pinfunction "A6_7") (pintype "input"))
      (node (ref "U2") (pin "23") (pinfunction "GPA2_23") (pintype "bidirectional"))
    )
    (net (code "105") (name "Net-(IC4A-A7)") (class "Default")
      (node (ref "IC4") (pin "8") (pinfunction "A7_8") (pintype "input"))
      (node (ref "U2") (pin "22") (pinfunction "GPA1_22") (pintype "bidirectional"))
    )
    (net (code "106") (name "Net-(IC4A-A8)") (class "Default")
      (node (ref "IC4") (pin "9") (pinfunction "A8_9") (pintype "input"))
      (node (ref "U2") (pin "21") (pinfunction "GPA0_21") (pintype "bidirectional"))
    )
    (net (code "107") (name "Net-(IC4A-Y1)") (class "Default")
      (node (ref "IC4") (pin "18") (pinfunction "Y1_18") (pintype "tri_state"))
      (node (ref "R26") (pin "1") (pinfunction "1_1") (pintype "passive"))
    )
    (net (code "108") (name "Net-(IC4A-Y2)") (class "Default")
      (node (ref "IC4") (pin "17") (pinfunction "Y2_17") (pintype "tri_state"))
      (node (ref "R27") (pin "2") (pinfunction "2_2") (pintype "passive"))
    )
    (net (code "109") (name "Net-(IC4A-Y3)") (class "Default")
      (node (ref "IC4") (pin "16") (pinfunction "Y3_16") (pintype "tri_state"))
      (node (ref "R25") (pin "1") (pinfunction "1_1") (pintype "passive"))
    )
    (net (code "110") (name "Net-(IC4A-Y4)") (class "Default")
      (node (ref "IC4") (pin "15") (pinfunction "Y4_15") (pintype "tri_state"))
      (node (ref "R24") (pin "1") (pinfunction "1_1") (pintype "passive"))
    )
    (net (code "111") (name "Net-(IC4A-Y5)") (class "Default")
      (node (ref "IC4") (pin "14") (pinfunction "Y5_14") (pintype "tri_state"))
      (node (ref "R23") (pin "1") (pinfunction "1_1") (pintype "passive"))
    )
    (net (code "112") (name "Net-(IC4A-Y6)") (class "Default")
      (node (ref "IC4") (pin "13") (pinfunction "Y6_13") (pintype "tri_state"))
      (node (ref "R22") (pin "1") (pinfunction "1_1") (pintype "passive"))
    )
    (net (code "113") (name "Net-(IC4A-Y7)") (class "Default")
      (node (ref "IC4") (pin "12") (pinfunction "Y7_12") (pintype "tri_state"))
      (node (ref "R21") (pin "1") (pinfunction "1_1") (pintype "passive"))
    )
    (net (code "114") (name "Net-(LED9-C)") (class "Default")
      (node (ref "LED9") (pin "K") (pinfunction "C_K") (pintype "passive"))
      (node (ref "S3") (pin "1") (pinfunction "O_1") (pintype "passive"))
    )
    (net (code "115") (name "Net-(LED9-PadA)") (class "Default")
      (node (ref "LED9") (pin "A") (pinfunction "A_A") (pintype "passive"))
      (node (ref "R6") (pin "1") (pinfunction "1_1") (pintype "passive"))
    )
    (net (code "116") (name "Net-(LED10-C)") (class "Default")
      (node (ref "LED10") (pin "K") (pinfunction "C_K") (pintype "passive"))
      (node (ref "S4") (pin "1") (pinfunction "O_1") (pintype "passive"))
    )
    (net (code "117") (name "Net-(LED10-PadA)") (class "Default")
      (node (ref "LED10") (pin "A") (pinfunction "A_A") (pintype "passive"))
      (node (ref "R5") (pin "1") (pinfunction "1_1") (pintype "passive"))
    )
    (net (code "118") (name "Net-(LED11-C)") (class "Default")
      (node (ref "LED11") (pin "K") (pinfunction "C_K") (pintype "passive"))
      (node (ref "S5") (pin "1") (pinfunction "O_1") (pintype "passive"))
    )
    (net (code "119") (name "Net-(LED11-PadA)") (class "Default")
      (node (ref "LED11") (pin "A") (pinfunction "A_A") (pintype "passive"))
      (node (ref "R4") (pin "1") (pinfunction "1_1") (pintype "passive"))
    )
    (net (code "120") (name "Net-(LED14-C)") (class "Default")
      (node (ref "LED14") (pin "K") (pinfunction "C_K") (pintype "passive"))
      (node (ref "S6") (pin "1") (pinfunction "O_1") (pintype "passive"))
    )
    (net (code "121") (name "Net-(LED14-PadA)") (class "Default")
      (node (ref "LED14") (pin "A") (pinfunction "A_A") (pintype "passive"))
      (node (ref "R3") (pin "1") (pinfunction "1_1") (pintype "passive"))
    )
    (net (code "122") (name "Net-(R1-S)") (class "Default")
      (node (ref "R1") (pin "2") (pinfunction "S_2") (pintype "passive"))
      (node (ref "U1") (pin "J1_7") (pinfunction "PB4_J1_7") (pintype "bidirectional"))
    )
    (net (code "123") (name "Net-(R2-S)") (class "Default")
      (node (ref "R2") (pin "2") (pinfunction "S_2") (pintype "passive"))
      (node (ref "U1") (pin "J1_2") (pinfunction "PB5_J1_2") (pintype "bidirectional"))
    )
    (net (code "124") (name "Net-(S1-P)") (class "Default")
      (node (ref "R35") (pin "2") (pinfunction "2_2") (pintype "passive"))
      (node (ref "R36") (pin "2") (pinfunction "2_2") (pintype "passive"))
      (node (ref "S1") (pin "3") (pinfunction "P_3") (pintype "passive"))
      (node (ref "S2") (pin "2") (pinfunction "S1_2") (pintype "passive"))
      (node (ref "U1") (pin "J1_1") (pinfunction "+3.3V_J1_1") (pintype "power_in"))
      (node (ref "U2") (pin "17") (pinfunction "A2_17") (pintype "input"))
      (node (ref "U2") (pin "18") (pinfunction "~{RESET}_18") (pintype "input"))
      (node (ref "U2") (pin "9") (pinfunction "VDD_9") (pintype "power_in"))
      (node (ref "U3") (pin "15") (pinfunction "A0_15") (pintype "input"))
      (node (ref "U3") (pin "18") (pinfunction "~{RESET}_18") (pintype "input"))
      (node (ref "U3") (pin "9") (pinfunction "VDD_9") (pintype "power_in"))
      (node (ref "U4") (pin "18") (pinfunction "~{RESET}_18") (pintype "input"))
      (node (ref "U4") (pin "9") (pinfunction "VDD_9") (pintype "power_in"))
      (node (ref "U5") (pin "16") (pinfunction "A1_16") (pintype "input"))
      (node (ref "U5") (pin "18") (pinfunction "~{RESET}_18") (pintype "input"))
      (node (ref "U5") (pin "9") (pinfunction "VDD_9") (pintype "power_in"))
    )
    (net (code "125") (name "Net-(S1-S)") (class "Default")
      (node (ref "R37") (pin "2") (pinfunction "2_2") (pintype "passive"))
      (node (ref "S1") (pin "1") (pinfunction "S_1") (pintype "passive"))
      (node (ref "S1") (pin "2") (pinfunction "S1_2") (pintype "passive"))
      (node (ref "U1") (pin "J2_3") (pinfunction "PE0_J2_3") (pintype "bidirectional"))
    )
    (net (code "126") (name "Net-(S2-P)") (class "Default")
      (node (ref "R38") (pin "2") (pinfunction "2_2") (pintype "passive"))
      (node (ref "S2") (pin "3") (pinfunction "P_3") (pintype "passive"))
      (node (ref "S2") (pin "4") (pinfunction "P1_4") (pintype "passive"))
      (node (ref "U1") (pin "J3_7") (pinfunction "PE1_J3_7") (pintype "bidirectional"))
    )
    (net (code "127") (name "Net-(S3-P)") (class "Default")
      (node (ref "S3") (pin "2") (pinfunction "P_2") (pintype "passive"))
      (node (ref "U1") (pin "J1_6") (pinfunction "PE5_J1_6") (pintype "bidirectional"))
    )
    (net (code "128") (name "Net-(S4-P)") (class "Default")
      (node (ref "S4") (pin "2") (pinfunction "P_2") (pintype "passive"))
      (node (ref "U1") (pin "J1_5") (pinfunction "PE4_J1_5") (pintype "bidirectional"))
    )
    (net (code "129") (name "Net-(S5-P)") (class "Default")
      (node (ref "S5") (pin "2") (pinfunction "P_2") (pintype "passive"))
      (node (ref "U1") (pin "J3_9") (pinfunction "PE3_J3_9") (pintype "bidirectional"))
    )
    (net (code "130") (name "Net-(S6-P)") (class "Default")
      (node (ref "S6") (pin "2") (pinfunction "P_2") (pintype "passive"))
      (node (ref "U1") (pin "J3_8") (pinfunction "PE2_J3_8") (pintype "bidirectional"))
    )
    (net (code "131") (name "Net-(U1-PB2)") (class "Default")
      (node (ref "R35") (pin "1") (pinfunction "1_1") (pintype "passive"))
      (node (ref "U1") (pin "J2_2") (pinfunction "PB2_J2_2") (pintype "bidirectional"))
      (node (ref "U2") (pin "12") (pinfunction "SCL_12") (pintype "input"))
      (node (ref "U3") (pin "12") (pinfunction "SCL_12") (pintype "input"))
      (node (ref "U4") (pin "12") (pinfunction "SCL_12") (pintype "input"))
      (node (ref "U5") (pin "12") (pinfunction "SCL_12") (pintype "input"))
    )
    (net (code "132") (name "Net-(U1-PB3)") (class "Default")
      (node (ref "R36") (pin "1") (pinfunction "1_1") (pintype "passive"))
      (node (ref "U1") (pin "J4_3") (pinfunction "PB3_J4_3") (pintype "bidirectional"))
      (node (ref "U2") (pin "13") (pinfunction "SDA_13") (pintype "bidirectional"))
      (node (ref "U3") (pin "13") (pinfunction "SDA_13") (pintype "bidirectional"))
      (node (ref "U4") (pin "13") (pinfunction "SDA_13") (pintype "bidirectional"))
      (node (ref "U5") (pin "13") (pinfunction "SDA_13") (pintype "bidirectional"))
    )
    (net (code "133") (name "unconnected-(D1-CK2-Pad8)") (class "Default")
      (node (ref "D1") (pin "8") (pinfunction "CK2_8") (pintype "passive"))
    )
    (net (code "134") (name "unconnected-(D1-DP-Pad5)") (class "Default")
      (node (ref "D1") (pin "5") (pinfunction "DP_5") (pintype "passive"))
    )
    (net (code "135") (name "unconnected-(D2-CK1-Pad3)") (class "Default")
      (node (ref "D2") (pin "3") (pinfunction "CK1_3") (pintype "passive"))
    )
    (net (code "136") (name "unconnected-(D2-DP-Pad5)") (class "Default")
      (node (ref "D2") (pin "5") (pinfunction "DP_5") (pintype "passive"))
    )
    (net (code "137") (name "unconnected-(D3-CK2-Pad8)") (class "Default")
      (node (ref "D3") (pin "8") (pinfunction "CK2_8") (pintype "passive"))
    )
    (net (code "138") (name "unconnected-(D3-DP-Pad5)") (class "Default")
      (node (ref "D3") (pin "5") (pinfunction "DP_5") (pintype "passive"))
    )
    (net (code "139") (name "unconnected-(D4-CK1-Pad3)") (class "Default")
      (node (ref "D4") (pin "3") (pinfunction "CK1_3") (pintype "passive"))
    )
    (net (code "140") (name "unconnected-(D4-DP-Pad5)") (class "Default")
      (node (ref "D4") (pin "5") (pinfunction "DP_5") (pintype "passive"))
    )
    (net (code "141") (name "unconnected-(DS1-NC-Pad6)") (class "Default")
      (node (ref "DS1") (pin "6") (pinfunction "NC_6") (pintype "no_connect"))
    )
    (net (code "142") (name "unconnected-(DS2-NC-Pad6)") (class "Default")
      (node (ref "DS2") (pin "6") (pinfunction "NC_6") (pintype "no_connect"))
    )
    (net (code "143") (name "unconnected-(DS3-NC-Pad6)") (class "Default")
      (node (ref "DS3") (pin "6") (pinfunction "NC_6") (pintype "no_connect"))
    )
    (net (code "144") (name "unconnected-(DS4-NC-Pad6)") (class "Default")
      (node (ref "DS4") (pin "6") (pinfunction "NC_6") (pintype "no_connect"))
    )
    (net (code "145") (name "unconnected-(J1-D+-Pad3)") (class "Default")
      (node (ref "J1") (pin "3") (pinfunction "D+_3") (pintype "bidirectional"))
    )
    (net (code "146") (name "unconnected-(J1-D--Pad2)") (class "Default")
      (node (ref "J1") (pin "2") (pinfunction "D-_2") (pintype "bidirectional"))
    )
    (net (code "147") (name "unconnected-(S1-P1-Pad4)") (class "Default")
      (node (ref "S1") (pin "4") (pinfunction "P1_4") (pintype "passive"))
    )
    (net (code "148") (name "unconnected-(S2-S-Pad1)") (class "Default")
      (node (ref "S2") (pin "1") (pinfunction "S_1") (pintype "passive"))
    )
    (net (code "149") (name "unconnected-(U1-PA2-PadJ2_10)") (class "Default")
      (node (ref "U1") (pin "J2_10") (pinfunction "PA2_J2_10") (pintype "bidirectional"))
    )
    (net (code "150") (name "unconnected-(U1-PA3-PadJ2_9)") (class "Default")
      (node (ref "U1") (pin "J2_9") (pinfunction "PA3_J2_9") (pintype "bidirectional"))
    )
    (net (code "151") (name "unconnected-(U1-PA4-PadJ2_8)") (class "Default")
      (node (ref "U1") (pin "J2_8") (pinfunction "PA4_J2_8") (pintype "bidirectional"))
    )
    (net (code "152") (name "unconnected-(U1-PA5-PadJ1_8)") (class "Default")
      (node (ref "U1") (pin "J1_8") (pinfunction "PA5_J1_8") (pintype "bidirectional"))
    )
    (net (code "153") (name "unconnected-(U1-PA6-PadJ1_9)") (class "Default")
      (node (ref "U1") (pin "J1_9") (pinfunction "PA6_J1_9") (pintype "bidirectional"))
    )
    (net (code "154") (name "unconnected-(U1-PA7-PadJ1_10)") (class "Default")
      (node (ref "U1") (pin "J1_10") (pinfunction "PA7_J1_10") (pintype "bidirectional"))
    )
    (net (code "155") (name "unconnected-(U1-PB0-PadJ1_3)") (class "Default")
      (node (ref "U1") (pin "J1_3") (pinfunction "PB0_J1_3") (pintype "bidirectional"))
    )
    (net (code "156") (name "unconnected-(U1-PB1-PadJ1_4)") (class "Default")
      (node (ref "U1") (pin "J1_4") (pinfunction "PB1_J1_4") (pintype "bidirectional"))
    )
    (net (code "157") (name "unconnected-(U1-PB6-PadJ2_7)") (class "Default")
      (node (ref "U1") (pin "J2_7") (pinfunction "PB6_J2_7") (pintype "bidirectional"))
    )
    (net (code "158") (name "unconnected-(U1-PB7-PadJ2_6)") (class "Default")
      (node (ref "U1") (pin "J2_6") (pinfunction "PB7_J2_6") (pintype "bidirectional"))
    )
    (net (code "159") (name "unconnected-(U1-PC4-PadJ4_4)") (class "Default")
      (node (ref "U1") (pin "J4_4") (pinfunction "PC4_J4_4") (pintype "bidirectional"))
    )
    (net (code "160") (name "unconnected-(U1-PC5-PadJ4_5)") (class "Default")
      (node (ref "U1") (pin "J4_5") (pinfunction "PC5_J4_5") (pintype "bidirectional"))
    )
    (net (code "161") (name "unconnected-(U1-PC6-PadJ4_6)") (class "Default")
      (node (ref "U1") (pin "J4_6") (pinfunction "PC6_J4_6") (pintype "bidirectional"))
    )
    (net (code "162") (name "unconnected-(U1-PC7-PadJ4_7)") (class "Default")
      (node (ref "U1") (pin "J4_7") (pinfunction "PC7_J4_7") (pintype "bidirectional"))
    )
    (net (code "163") (name "unconnected-(U1-PD0-PadJ3_3)") (class "Default")
      (node (ref "U1") (pin "J3_3") (pinfunction "PD0_J3_3") (pintype "bidirectional"))
    )
    (net (code "164") (name "unconnected-(U1-PD1-PadJ3_4)") (class "Default")
      (node (ref "U1") (pin "J3_4") (pinfunction "PD1_J3_4") (pintype "bidirectional"))
    )
    (net (code "165") (name "unconnected-(U1-PD2-PadJ3_5)") (class "Default")
      (node (ref "U1") (pin "J3_5") (pinfunction "PD2_J3_5") (pintype "bidirectional"))
    )
    (net (code "166") (name "unconnected-(U1-PD3-PadJ3_6)") (class "Default")
      (node (ref "U1") (pin "J3_6") (pinfunction "PD3_J3_6") (pintype "bidirectional"))
    )
    (net (code "167") (name "unconnected-(U1-PD6-PadJ4_8)") (class "Default")
      (node (ref "U1") (pin "J4_8") (pinfunction "PD6_J4_8") (pintype "bidirectional"))
    )
    (net (code "168") (name "unconnected-(U1-PD7-PadJ4_9)") (class "Default")
      (node (ref "U1") (pin "J4_9") (pinfunction "PD7_J4_9") (pintype "bidirectional"))
    )
    (net (code "169") (name "unconnected-(U1-PF0-PadJ2_4)") (class "Default")
      (node (ref "U1") (pin "J2_4") (pinfunction "PF0_J2_4") (pintype "bidirectional"))
    )
    (net (code "170") (name "unconnected-(U1-PF1-PadJ3_10)") (class "Default")
      (node (ref "U1") (pin "J3_10") (pinfunction "PF1_J3_10") (pintype "bidirectional"))
    )
    (net (code "171") (name "unconnected-(U1-PF2-PadJ4_1)") (class "Default")
      (node (ref "U1") (pin "J4_1") (pinfunction "PF2_J4_1") (pintype "bidirectional"))
    )
    (net (code "172") (name "unconnected-(U1-PF3-PadJ4_2)") (class "Default")
      (node (ref "U1") (pin "J4_2") (pinfunction "PF3_J4_2") (pintype "bidirectional"))
    )
    (net (code "173") (name "unconnected-(U1-PF4-PadJ4_10)") (class "Default")
      (node (ref "U1") (pin "J4_10") (pinfunction "PF4_J4_10") (pintype "bidirectional"))
    )
    (net (code "174") (name "unconnected-(U1-~{TARGETRST}-PadJ2_5)") (class "Default")
      (node (ref "U1") (pin "J2_5") (pinfunction "~{TARGETRST}_J2_5") (pintype "input"))
    )
    (net (code "175") (name "unconnected-(U2-GPB0-Pad1)") (class "Default")
      (node (ref "U2") (pin "1") (pinfunction "GPB0_1") (pintype "bidirectional"))
    )
    (net (code "176") (name "unconnected-(U2-GPB1-Pad2)") (class "Default")
      (node (ref "U2") (pin "2") (pinfunction "GPB1_2") (pintype "bidirectional"))
    )
    (net (code "177") (name "unconnected-(U2-GPB2-Pad3)") (class "Default")
      (node (ref "U2") (pin "3") (pinfunction "GPB2_3") (pintype "bidirectional"))
    )
    (net (code "178") (name "unconnected-(U2-INTA-Pad20)") (class "Default")
      (node (ref "U2") (pin "20") (pinfunction "INTA_20") (pintype "output"))
    )
    (net (code "179") (name "unconnected-(U2-INTB-Pad19)") (class "Default")
      (node (ref "U2") (pin "19") (pinfunction "INTB_19") (pintype "output"))
    )
    (net (code "180") (name "unconnected-(U3-GPB0-Pad1)") (class "Default")
      (node (ref "U3") (pin "1") (pinfunction "GPB0_1") (pintype "bidirectional"))
    )
    (net (code "181") (name "unconnected-(U3-GPB1-Pad2)") (class "Default")
      (node (ref "U3") (pin "2") (pinfunction "GPB1_2") (pintype "bidirectional"))
    )
    (net (code "182") (name "unconnected-(U3-GPB2-Pad3)") (class "Default")
      (node (ref "U3") (pin "3") (pinfunction "GPB2_3") (pintype "bidirectional"))
    )
    (net (code "183") (name "unconnected-(U3-GPB3-Pad4)") (class "Default")
      (node (ref "U3") (pin "4") (pinfunction "GPB3_4") (pintype "bidirectional"))
    )
    (net (code "184") (name "unconnected-(U3-GPB4-Pad5)") (class "Default")
      (node (ref "U3") (pin "5") (pinfunction "GPB4_5") (pintype "bidirectional"))
    )
    (net (code "185") (name "unconnected-(U3-INTA-Pad20)") (class "Default")
      (node (ref "U3") (pin "20") (pinfunction "INTA_20") (pintype "output"))
    )
    (net (code "186") (name "unconnected-(U3-INTB-Pad19)") (class "Default")
      (node (ref "U3") (pin "19") (pinfunction "INTB_19") (pintype "output"))
    )
    (net (code "187") (name "unconnected-(U4-GPB0-Pad1)") (class "Default")
      (node (ref "U4") (pin "1") (pinfunction "GPB0_1") (pintype "bidirectional"))
    )
    (net (code "188") (name "unconnected-(U4-GPB1-Pad2)") (class "Default")
      (node (ref "U4") (pin "2") (pinfunction "GPB1_2") (pintype "bidirectional"))
    )
    (net (code "189") (name "unconnected-(U4-GPB2-Pad3)") (class "Default")
      (node (ref "U4") (pin "3") (pinfunction "GPB2_3") (pintype "bidirectional"))
    )
    (net (code "190") (name "unconnected-(U4-INTA-Pad20)") (class "Default")
      (node (ref "U4") (pin "20") (pinfunction "INTA_20") (pintype "output"))
    )
    (net (code "191") (name "unconnected-(U4-INTB-Pad19)") (class "Default")
      (node (ref "U4") (pin "19") (pinfunction "INTB_19") (pintype "output"))
    )
    (net (code "192") (name "unconnected-(U5-GPB0-Pad1)") (class "Default")
      (node (ref "U5") (pin "1") (pinfunction "GPB0_1") (pintype "bidirectional"))
    )
    (net (code "193") (name "unconnected-(U5-GPB1-Pad2)") (class "Default")
      (node (ref "U5") (pin "2") (pinfunction "GPB1_2") (pintype "bidirectional"))
    )
    (net (code "194") (name "unconnected-(U5-GPB2-Pad3)") (class "Default")
      (node (ref "U5") (pin "3") (pinfunction "GPB2_3") (pintype "bidirectional"))
    )
    (net (code "195") (name "unconnected-(U5-GPB3-Pad4)") (class "Default")
      (node (ref "U5") (pin "4") (pinfunction "GPB3_4") (pintype "bidirectional"))
    )
    (net (code "196") (name "unconnected-(U5-GPB4-Pad5)") (class "Default")
      (node (ref "U5") (pin "5") (pinfunction "GPB4_5") (pintype "bidirectional"))
    )
    (net (code "197") (name "unconnected-(U5-INTA-Pad20)") (class "Default")
      (node (ref "U5") (pin "20") (pinfunction "INTA_20") (pintype "output"))
    )
    (net (code "198") (name "unconnected-(U5-INTB-Pad19)") (class "Default")
      (node (ref "U5") (pin "19") (pinfunction "INTB_19") (pintype "output"))
    )
  )
)
